# PIR.net
KiCad netlist of a schematic drawn in EAGLE
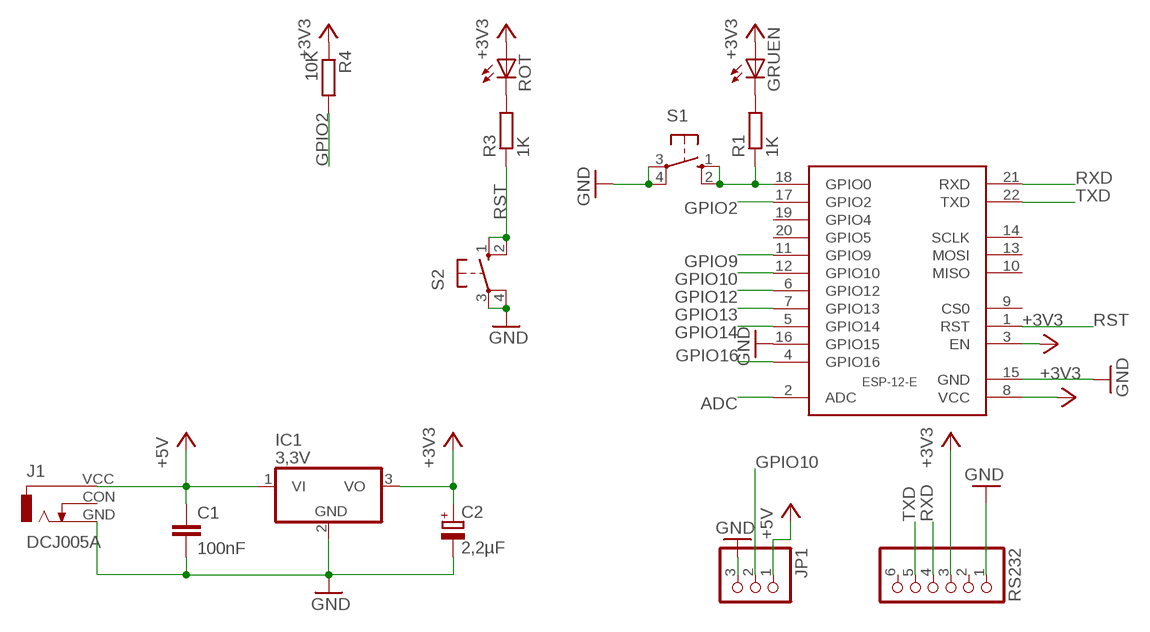
[diagram p0: schematic, sheet 1]

(export (version "E")
  (design (tool "Eeschema 10.0.6"))
  (components
    (comp (ref "C1")
      (value "100nF")
      (footprint "eagle-import:C050-030X075")
      (libsource (lib "eagle-import") (part "C-EU050-030X075"))
    )
    (comp (ref "C2")
      (value "2,2µF")
      (footprint "eagle-import:E2,5-6")
      (libsource (lib "eagle-import") (part "CPOL-EUE2.5-6"))
    )
    (comp (ref "GRUEN")
      (value "LED5MM")
      (footprint "eagle-import:LED5MM")
      (libsource (lib "eagle-import") (part "LED5MM"))
    )
    (comp (ref "IC1")
      (value "3,3V")
      (footprint "eagle-import:TO220V")
      (libsource (lib "eagle-import") (part "78TV05"))
    )
    (comp (ref "J1")
      (value "DCJ005A")
      (footprint "eagle-import:DC005A")
      (libsource (lib "eagle-import") (part "DCJ005A"))
    )
    (comp (ref "JP1")
      (value "PINHD-1X3")
      (footprint "eagle-import:1X03")
      (libsource (lib "eagle-import") (part "PINHD-1X3"))
    )
    (comp (ref "R1")
      (value "1K")
      (footprint "eagle-import:0207_10")
      (libsource (lib "eagle-import") (part "R-EU_0207/10"))
    )
    (comp (ref "R3")
      (value "1K")
      (footprint "eagle-import:0207_10")
      (libsource (lib "eagle-import") (part "R-EU_0207/10"))
    )
    (comp (ref "R4")
      (value "10K")
      (footprint "eagle-import:0207_10")
      (libsource (lib "eagle-import") (part "R-EU_0207/10"))
    )
    (comp (ref "ROT")
      (value "LED5MM")
      (footprint "eagle-import:LED5MM")
      (libsource (lib "eagle-import") (part "LED5MM"))
    )
    (comp (ref "RS232")
      (value "PINHD-1X6")
      (footprint "eagle-import:1X06")
      (libsource (lib "eagle-import") (part "PINHD-1X6"))
    )
    (comp (ref "S1")
      (value "10-XX")
      (footprint "eagle-import:B3F-10XX")
      (fields (field (name "MPN") "B3F-1000"))
      (libsource (lib "eagle-import") (part "10-XX"))
    )
    (comp (ref "S2")
      (value "10-XX")
      (footprint "eagle-import:B3F-10XX")
      (fields (field (name "MPN") "B3F-1000"))
      (libsource (lib "eagle-import") (part "10-XX"))
    )
    (comp (ref "U$1")
      (value "ESP-12-E")
      (footprint "eagle-import:ESP-12-E")
      (libsource (lib "eagle-import") (part "ESP-12-E"))
    )
  )
  (nets
    (net (code "1") (name "+3V3") (class "Default")
      (node (ref "C2") (pin "+") (pinfunction "+_+") (pintype "passive"))
      (node (ref "GRUEN") (pin "A") (pinfunction "A_A") (pintype "passive"))
      (node (ref "IC1") (pin "3") (pinfunction "VO_3") (pintype "passive"))
      (node (ref "R4") (pin "1") (pinfunction "1_1") (pintype "passive"))
      (node (ref "ROT") (pin "A") (pinfunction "A_A") (pintype "passive"))
      (node (ref "RS232") (pin "3") (pinfunction "3_3") (pintype "passive"))
      (node (ref "U$1") (pin "3") (pinfunction "EN_3") (pintype "bidirectional"))
      (node (ref "U$1") (pin "8") (pinfunction "VCC_8") (pintype "power_in"))
    )
    (net (code "2") (name "+5V") (class "Default")
      (node (ref "C1") (pin "1") (pinfunction "1_1") (pintype "passive"))
      (node (ref "IC1") (pin "1") (pinfunction "VI_1") (pintype "input"))
      (node (ref "J1") (pin "VCC") (pinfunction "1_VCC") (pintype "passive"))
      (node (ref "JP1") (pin "1") (pinfunction "1_1") (pintype "passive"))
    )
    (net (code "3") (name "/ADC") (class "Default")
      (node (ref "U$1") (pin "2") (pinfunction "ADC_2") (pintype "bidirectional"))
    )
    (net (code "4") (name "/GPIO2") (class "Default")
      (node (ref "R4") (pin "2") (pinfunction "2_2") (pintype "passive"))
      (node (ref "U$1") (pin "17") (pinfunction "GPIO2_17") (pintype "bidirectional"))
    )
    (net (code "5") (name "/GPIO9") (class "Default")
      (node (ref "U$1") (pin "11") (pinfunction "GPIO9_11") (pintype "bidirectional"))
    )
    (net (code "6") (name "/GPIO10") (class "Default")
      (node (ref "JP1") (pin "2") (pinfunction "2_2") (pintype "passive"))
      (node (ref "U$1") (pin "12") (pinfunction "GPIO10_12") (pintype "bidirectional"))
    )
    (net (code "7") (name "/GPIO12") (class "Default")
      (node (ref "U$1") (pin "6") (pinfunction "GPIO12_6") (pintype "bidirectional"))
    )
    (net (code "8") (name "/GPIO13") (class "Default")
      (node (ref "U$1") (pin "7") (pinfunction "GPIO13_7") (pintype "bidirectional"))
    )
    (net (code "9") (name "/GPIO14") (class "Default")
      (node (ref "U$1") (pin "5") (pinfunction "GPIO14_5") (pintype "bidirectional"))
    )
    (net (code "10") (name "/GPIO16") (class "Default")
      (node (ref "U$1") (pin "4") (pinfunction "GPIO16_4") (pintype "bidirectional"))
    )
    (net (code "11") (name "/RST") (class "Default")
      (node (ref "R3") (pin "1") (pinfunction "1_1") (pintype "passive"))
      (node (ref "S2") (pin "1") (pinfunction "S_1") (pintype "passive"))
      (node (ref "S2") (pin "2") (pinfunction "S1_2") (pintype "passive"))
      (node (ref "U$1") (pin "1") (pinfunction "RST_1") (pintype "bidirectional"))
    )
    (net (code "12") (name "/RXD") (class "Default")
      (node (ref "RS232") (pin "4") (pinfunction "4_4") (pintype "passive"))
      (node (ref "U$1") (pin "21") (pinfunction "RXD_21") (pintype "bidirectional"))
    )
    (net (code "13") (name "/TXD") (class "Default")
      (node (ref "RS232") (pin "5") (pinfunction "5_5") (pintype "passive"))
      (node (ref "U$1") (pin "22") (pinfunction "TXD_22") (pintype "bidirectional"))
    )
    (net (code "14") (name "GND") (class "Default")
      (node (ref "C1") (pin "2") (pinfunction "2_2") (pintype "passive"))
      (node (ref "C2") (pin "-") (pinfunction "-_-") (pintype "passive"))
      (node (ref "IC1") (pin "2") (pinfunction "GND_2") (pintype "passive"))
      (node (ref "J1") (pin "GND") (pinfunction "3_GND") (pintype "passive"))
      (node (ref "JP1") (pin "3") (pinfunction "3_3") (pintype "passive"))
      (node (ref "RS232") (pin "1") (pinfunction "1_1") (pintype "passive"))
      (node (ref "S1") (pin "3") (pinfunction "P_3") (pintype "passive"))
      (node (ref "S1") (pin "4") (pinfunction "P1_4") (pintype "passive"))
      (node (ref "S2") (pin "3") (pinfunction "P_3") (pintype "passive"))
      (node (ref "S2") (pin "4") (pinfunction "P1_4") (pintype "passive"))
      (node (ref "U$1") (pin "15") (pinfunction "GND_15") (pintype "power_in"))
      (node (ref "U$1") (pin "16") (pinfunction "GPIO15_16") (pintype "bidirectional"))
    )
    (net (code "15") (name "Net-(GRUEN-C)") (class "Default")
      (node (ref "GRUEN") (pin "K") (pinfunction "C_K") (pintype "passive"))
      (node (ref "R1") (pin "2") (pinfunction "2_2") (pintype "passive"))
    )
    (net (code "16") (name "Net-(ROT-C)") (class "Default")
      (node (ref "R3") (pin "2") (pinfunction "2_2") (pintype "passive"))
      (node (ref "ROT") (pin "K") (pinfunction "C_K") (pintype "passive"))
    )
    (net (code "17") (name "Net-(S1-S)") (class "Default")
      (node (ref "R1") (pin "1") (pinfunction "1_1") (pintype "passive"))
      (node (ref "S1") (pin "1") (pinfunction "S_1") (pintype "passive"))
      (node (ref "S1") (pin "2") (pinfunction "S1_2") (pintype "passive"))
      (node (ref "U$1") (pin "18") (pinfunction "GPIO0_18") (pintype "bidirectional"))
    )
    (net (code "18") (name "unconnected-(J1-2-PadCON)") (class "Default")
      (node (ref "J1") (pin "CON") (pinfunction "2_CON") (pintype "passive"))
    )
    (net (code "19") (name "unconnected-(RS232-Pad2)") (class "Default")
      (node (ref "RS232") (pin "2") (pinfunction "2_2") (pintype "passive"))
    )
    (net (code "20") (name "unconnected-(RS232-Pad6)") (class "Default")
      (node (ref "RS232") (pin "6") (pinfunction "6_6") (pintype "passive"))
    )
    (net (code "21") (name "unconnected-(U$1-CS0-Pad9)") (class "Default")
      (node (ref "U$1") (pin "9") (pinfunction "CS0_9") (pintype "bidirectional"))
    )
    (net (code "22") (name "unconnected-(U$1-GPIO4-Pad19)") (class "Default")
      (node (ref "U$1") (pin "19") (pinfunction "GPIO4_19") (pintype "bidirectional"))
    )
    (net (code "23") (name "unconnected-(U$1-GPIO5-Pad20)") (class "Default")
      (node (ref "U$1") (pin "20") (pinfunction "GPIO5_20") (pintype "bidirectional"))
    )
    (net (code "24") (name "unconnected-(U$1-MISO-Pad10)") (class "Default")
      (node (ref "U$1") (pin "10") (pinfunction "MISO_10") (pintype "bidirectional"))
    )
    (net (code "25") (name "unconnected-(U$1-MOSI-Pad13)") (class "Default")
      (node (ref "U$1") (pin "13") (pinfunction "MOSI_13") (pintype "bidirectional"))
    )
    (net (code "26") (name "unconnected-(U$1-SCLK-Pad14)") (class "Default")
      (node (ref "U$1") (pin "14") (pinfunction "SCLK_14") (pintype "bidirectional"))
    )
  )
)
